# Sheet1.net
KiCad netlist of a schematic drawn in Altium Designer
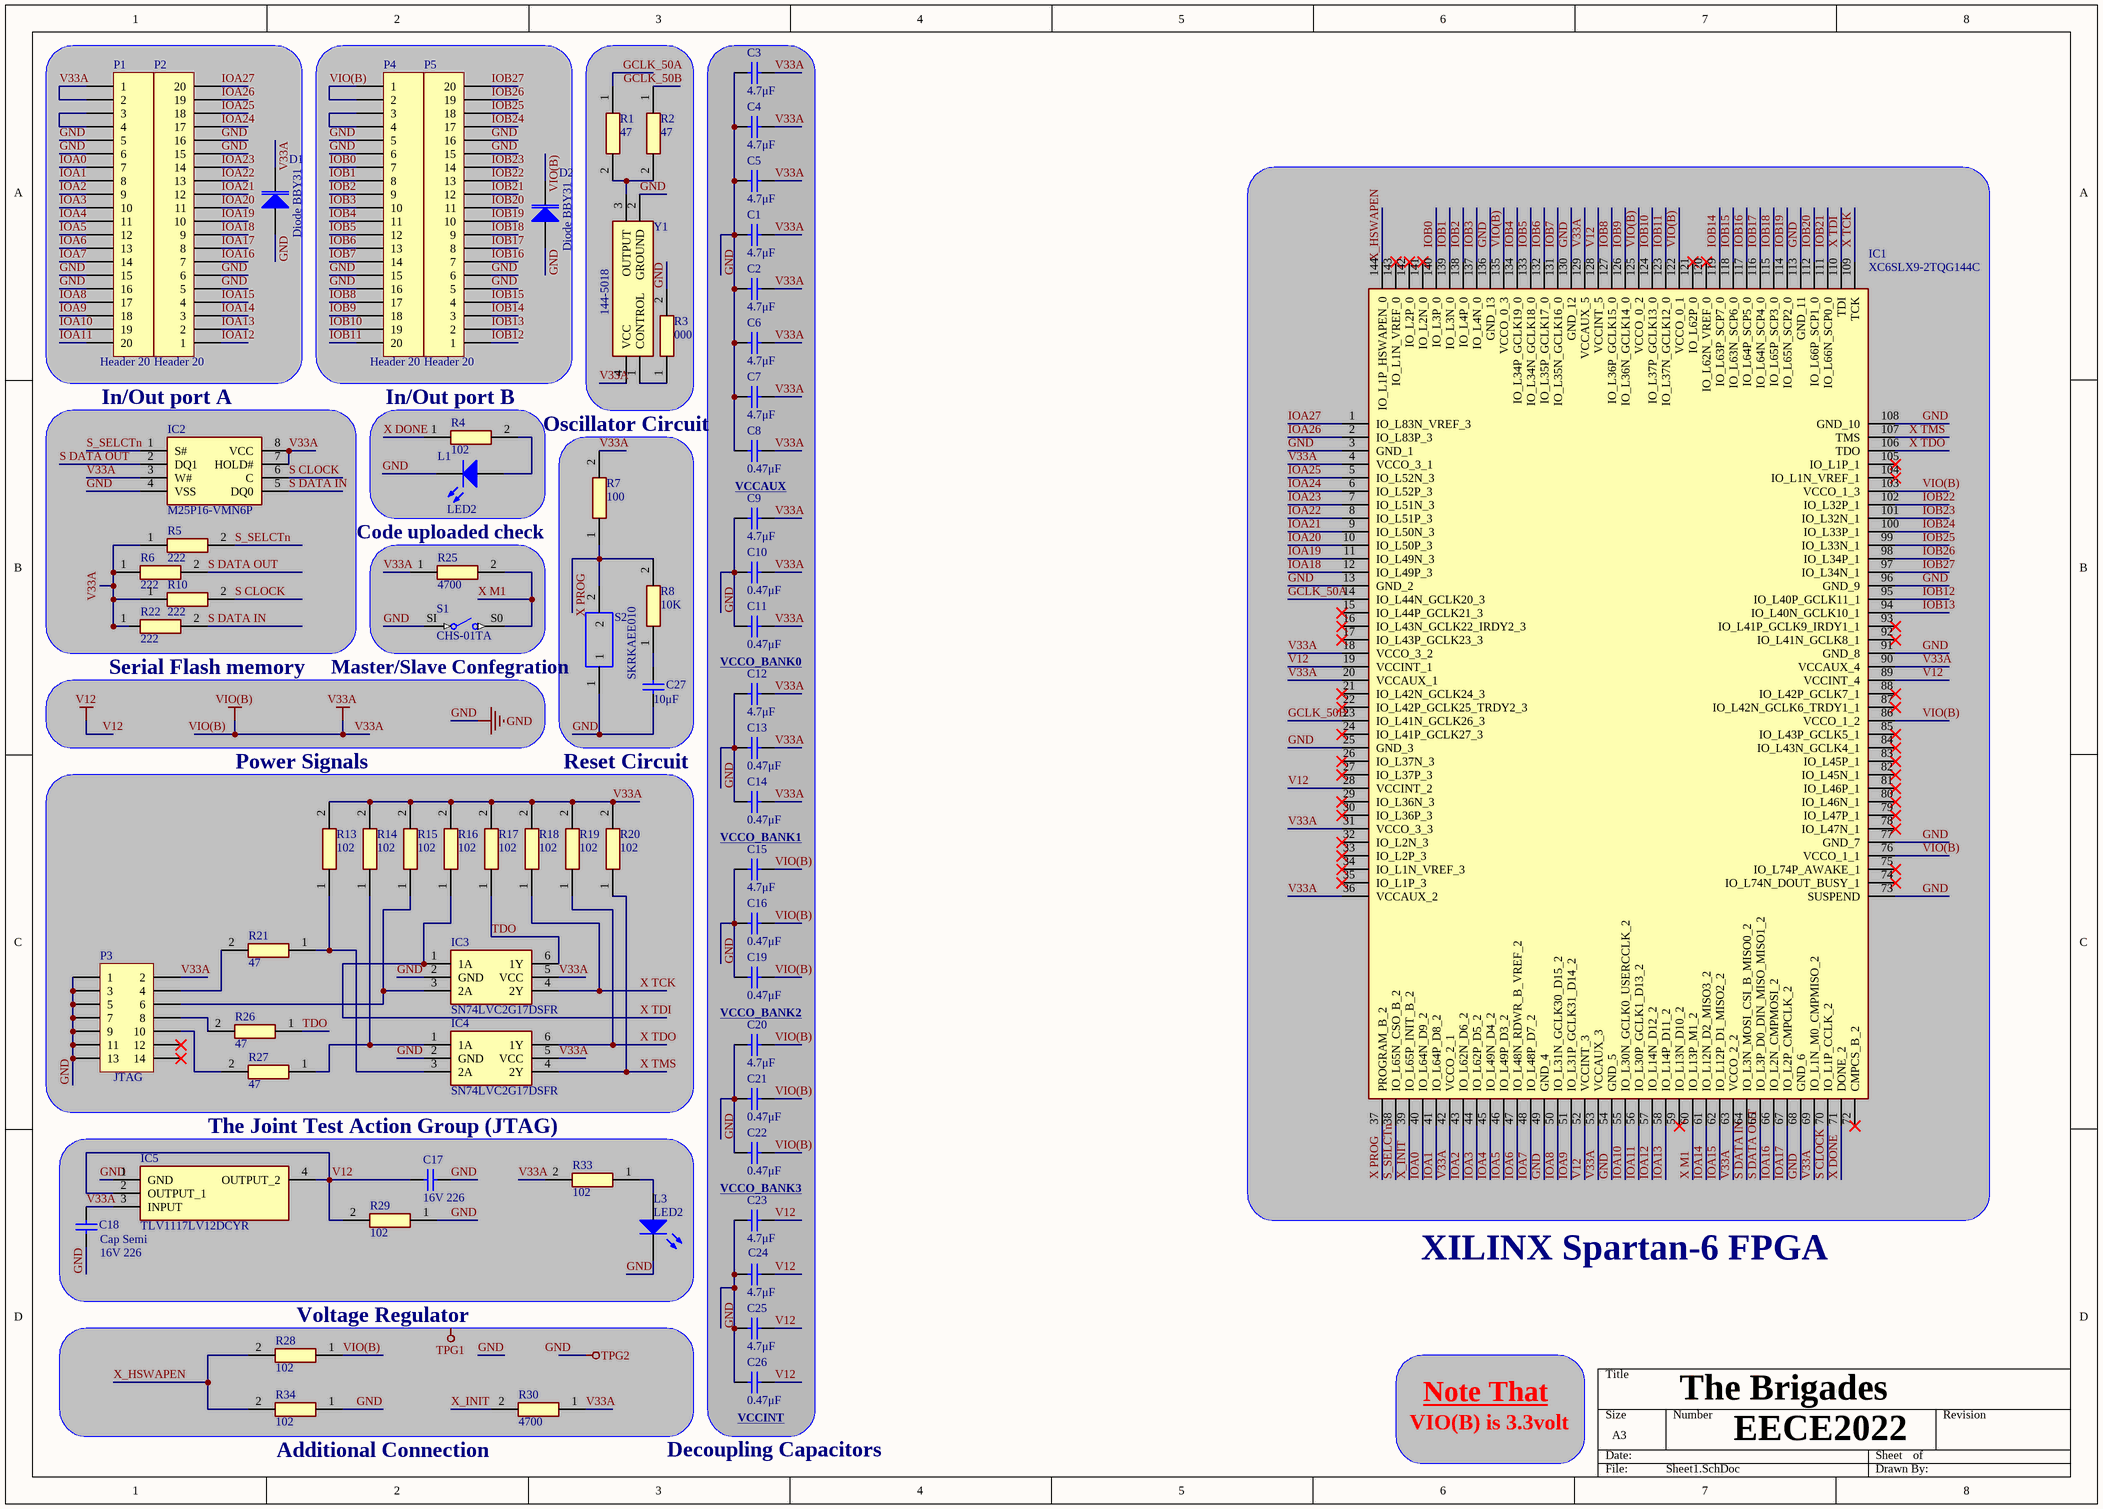
[diagram p0: Sheet1.SchDoc]

(export (version "E")
  (design (tool "Eeschema 10.0.6"))
  (components
    (comp (ref "C1")
      (value "4.7μF")
      (footprint "0402")
      (description "Capacitor (Semiconductor SIM Model)")
      (fields (field (name "PUBLISHER") "Altium Limited"))
      (libsource (lib "Miscellaneous Devices") (part "Cap Semi"))
    )
    (comp (ref "C2")
      (value "4.7μF")
      (footprint "0402")
      (description "Capacitor (Semiconductor SIM Model)")
      (fields (field (name "PUBLISHER") "Altium Limited"))
      (libsource (lib "Miscellaneous Devices") (part "Cap Semi"))
    )
    (comp (ref "C3")
      (value "4.7μF")
      (footprint "0402")
      (description "Capacitor (Semiconductor SIM Model)")
      (fields (field (name "PUBLISHER") "Altium Limited"))
      (libsource (lib "Miscellaneous Devices") (part "Cap Semi"))
    )
    (comp (ref "C4")
      (value "4.7μF")
      (footprint "0402")
      (description "Capacitor (Semiconductor SIM Model)")
      (fields (field (name "PUBLISHER") "Altium Limited"))
      (libsource (lib "Miscellaneous Devices") (part "Cap Semi"))
    )
    (comp (ref "C5")
      (value "4.7μF")
      (footprint "0402")
      (description "Capacitor (Semiconductor SIM Model)")
      (fields (field (name "PUBLISHER") "Altium Limited"))
      (libsource (lib "Miscellaneous Devices") (part "Cap Semi"))
    )
    (comp (ref "C6")
      (value "4.7μF")
      (footprint "0402")
      (description "Capacitor (Semiconductor SIM Model)")
      (fields (field (name "PUBLISHER") "Altium Limited"))
      (libsource (lib "Miscellaneous Devices") (part "Cap Semi"))
    )
    (comp (ref "C7")
      (value "4.7μF")
      (footprint "0402")
      (description "Capacitor (Semiconductor SIM Model)")
      (fields (field (name "PUBLISHER") "Altium Limited"))
      (libsource (lib "Miscellaneous Devices") (part "Cap Semi"))
    )
    (comp (ref "C8")
      (value "0.47μF")
      (footprint "0402")
      (description "Capacitor (Semiconductor SIM Model)")
      (fields (field (name "PUBLISHER") "Altium Limited"))
      (libsource (lib "Miscellaneous Devices") (part "Cap Semi"))
    )
    (comp (ref "C9")
      (value "4.7μF")
      (footprint "0402")
      (description "Capacitor (Semiconductor SIM Model)")
      (fields (field (name "PUBLISHER") "Altium Limited"))
      (libsource (lib "Miscellaneous Devices") (part "Cap Semi"))
    )
    (comp (ref "C10")
      (value "0.47μF")
      (footprint "0402")
      (description "Capacitor (Semiconductor SIM Model)")
      (fields (field (name "PUBLISHER") "Altium Limited"))
      (libsource (lib "Miscellaneous Devices") (part "Cap Semi"))
    )
    (comp (ref "C11")
      (value "0.47μF")
      (footprint "0402")
      (description "Capacitor (Semiconductor SIM Model)")
      (fields (field (name "PUBLISHER") "Altium Limited"))
      (libsource (lib "Miscellaneous Devices") (part "Cap Semi"))
    )
    (comp (ref "C12")
      (value "4.7μF")
      (footprint "0402")
      (description "Capacitor (Semiconductor SIM Model)")
      (fields (field (name "PUBLISHER") "Altium Limited"))
      (libsource (lib "Miscellaneous Devices") (part "Cap Semi"))
    )
    (comp (ref "C13")
      (value "0.47μF")
      (footprint "0402")
      (description "Capacitor (Semiconductor SIM Model)")
      (fields (field (name "PUBLISHER") "Altium Limited"))
      (libsource (lib "Miscellaneous Devices") (part "Cap Semi"))
    )
    (comp (ref "C14")
      (value "0.47μF")
      (footprint "0402")
      (description "Capacitor (Semiconductor SIM Model)")
      (fields (field (name "PUBLISHER") "Altium Limited"))
      (libsource (lib "Miscellaneous Devices") (part "Cap Semi"))
    )
    (comp (ref "C15")
      (value "4.7μF")
      (footprint "0402")
      (description "Capacitor (Semiconductor SIM Model)")
      (fields (field (name "PUBLISHER") "Altium Limited"))
      (libsource (lib "Miscellaneous Devices") (part "Cap Semi"))
    )
    (comp (ref "C16")
      (value "0.47μF")
      (footprint "0402")
      (description "Capacitor (Semiconductor SIM Model)")
      (fields (field (name "PUBLISHER") "Altium Limited"))
      (libsource (lib "Miscellaneous Devices") (part "Cap Semi"))
    )
    (comp (ref "C17")
      (value "16V 226")
      (footprint "0402")
      (description "Capacitor (Semiconductor SIM Model)")
      (fields (field (name "PUBLISHER") "Altium Limited"))
      (libsource (lib "Miscellaneous Devices") (part "Cap Semi"))
    )
    (comp (ref "C18")
      (value "Cap Semi")
      (footprint "0402")
      (description "Capacitor (Semiconductor SIM Model)")
      (fields (field (name "ALTIUM_VALUE") "16V 226") (field (name "PUBLISHER") "Altium Limited"))
      (libsource (lib "Miscellaneous Devices") (part "Cap Semi"))
    )
    (comp (ref "C19")
      (value "0.47μF")
      (footprint "0402")
      (description "Capacitor (Semiconductor SIM Model)")
      (fields (field (name "PUBLISHER") "Altium Limited"))
      (libsource (lib "Miscellaneous Devices") (part "Cap Semi"))
    )
    (comp (ref "C20")
      (value "4.7μF")
      (footprint "0402")
      (description "Capacitor (Semiconductor SIM Model)")
      (fields (field (name "PUBLISHER") "Altium Limited"))
      (libsource (lib "Miscellaneous Devices") (part "Cap Semi"))
    )
    (comp (ref "C21")
      (value "0.47μF")
      (footprint "0402")
      (description "Capacitor (Semiconductor SIM Model)")
      (fields (field (name "PUBLISHER") "Altium Limited"))
      (libsource (lib "Miscellaneous Devices") (part "Cap Semi"))
    )
    (comp (ref "C22")
      (value "0.47μF")
      (footprint "0402")
      (description "Capacitor (Semiconductor SIM Model)")
      (fields (field (name "PUBLISHER") "Altium Limited"))
      (libsource (lib "Miscellaneous Devices") (part "Cap Semi"))
    )
    (comp (ref "C23")
      (value "4.7μF")
      (footprint "0402")
      (description "Capacitor (Semiconductor SIM Model)")
      (fields (field (name "PUBLISHER") "Altium Limited"))
      (libsource (lib "Miscellaneous Devices") (part "Cap Semi"))
    )
    (comp (ref "C24")
      (value "4.7μF")
      (footprint "0402")
      (description "Capacitor (Semiconductor SIM Model)")
      (fields (field (name "PUBLISHER") "Altium Limited"))
      (libsource (lib "Miscellaneous Devices") (part "Cap Semi"))
    )
    (comp (ref "C25")
      (value "4.7μF")
      (footprint "0402")
      (description "Capacitor (Semiconductor SIM Model)")
      (fields (field (name "PUBLISHER") "Altium Limited"))
      (libsource (lib "Miscellaneous Devices") (part "Cap Semi"))
    )
    (comp (ref "C26")
      (value "0.47μF")
      (footprint "0402")
      (description "Capacitor (Semiconductor SIM Model)")
      (fields (field (name "PUBLISHER") "Altium Limited"))
      (libsource (lib "Miscellaneous Devices") (part "Cap Semi"))
    )
    (comp (ref "C27")
      (value "10μF")
      (footprint "0402")
      (description "Capacitor (Semiconductor SIM Model)")
      (fields (field (name "PUBLISHER") "Altium Limited"))
      (libsource (lib "Miscellaneous Devices") (part "Cap Semi"))
    )
    (comp (ref "D1")
      (value "Diode BBY31")
      (footprint "SOT23_N")
      (description "SOT23 Silicon Planar Variable Capacitance Diode")
      (fields (field (name "PUBLISHER") "Altium Limited"))
      (libsource (lib "Miscellaneous Devices") (part "Diode BBY31"))
    )
    (comp (ref "D2")
      (value "Diode BBY31")
      (footprint "SOT23_N")
      (description "SOT23 Silicon Planar Variable Capacitance Diode")
      (fields (field (name "PUBLISHER") "Altium Limited"))
      (libsource (lib "Miscellaneous Devices") (part "Diode BBY31"))
    )
    (comp (ref "IC1")
      (value "XC6SLX9-2TQG144C")
      (footprint "SamacSys:QFP50P2200X2200X160-144N")
      (description "Integrated Circuit")
      (fields
        (field (name "MOUSER PART NUMBER") "217-XC6SLX9-2TQG144C")
        (field (name "RS PART NUMBER") "7276011P")
      )
      (libsource (lib "*") (part "XC6SLX9-2TQG144C"))
    )
    (comp (ref "IC2")
      (value "M25P16-VMN6P")
      (footprint "SamacSys:SOIC127P600X175-8N")
      (description "Integrated Circuit")
      (fields (field (name "MOUSER PART NUMBER") "340-180484") (field (name "RS PART NUMBER") "7824601P"))
      (libsource (lib "*") (part "M25P16-VMN6P"))
    )
    (comp (ref "IC3")
      (value "SN74LVC2G17DSFR")
      (footprint "SamacSys:SON35P100X100X40-6N")
      (description "Integrated Circuit")
      (fields (field (name "MOUSER PART NUMBER") "595-SN74LVC2G17DSFR"))
      (libsource (lib "*") (part "SN74LVC2G17DSFR"))
    )
    (comp (ref "IC4")
      (value "SN74LVC2G17DSFR")
      (footprint "SamacSys:SON35P100X100X40-6N")
      (description "Integrated Circuit")
      (fields (field (name "MOUSER PART NUMBER") "595-SN74LVC2G17DSFR"))
      (libsource (lib "*") (part "SN74LVC2G17DSFR"))
    )
    (comp (ref "IC5")
      (value "TLV1117LV12DCYR")
      (footprint "SamacSys:SOT230P700X180-4N")
      (description "Integrated Circuit")
      (fields
        (field (name "MOUSER PART NUMBER") "595-TLV1117LV12DCYR")
        (field (name "RS PART NUMBER") "8253628P")
      )
      (libsource (lib "*") (part "TLV1117LV12DCYR"))
    )
    (comp (ref "L1")
      (value "LED2")
      (footprint "3.2X1.6X1.1")
      (description "Typical RED, GREEN, YELLOW, AMBER GaAs LED")
      (fields (field (name "PUBLISHER") "Altium Limited"))
      (libsource (lib "Miscellaneous Devices") (part "LED2"))
    )
    (comp (ref "L3")
      (value "LED2")
      (footprint "3.2X1.6X1.1")
      (description "Typical RED, GREEN, YELLOW, AMBER GaAs LED")
      (fields (field (name "PUBLISHER") "Altium Limited"))
      (libsource (lib "Miscellaneous Devices") (part "LED2"))
    )
    (comp (ref "P1")
      (value "Header 20")
      (footprint "HDR1X20")
      (description "Header, 20-Pin")
      (fields (field (name "PUBLISHER") "Altium Limited"))
      (libsource (lib "") (part "Header 20_1"))
    )
    (comp (ref "P2")
      (value "Header 20")
      (footprint "HDR1X20")
      (description "Header, 20-Pin")
      (fields (field (name "PUBLISHER") "Altium Limited"))
      (libsource (lib "Miscellaneous Connectors") (part "Header 20"))
    )
    (comp (ref "P3")
      (value "JTAG")
      (footprint "HDR2X7H")
      (description "Header, 7-Pin, Dual row, Right Angle")
      (fields (field (name "PUBLISHER") "Altium Limited"))
      (libsource (lib "Miscellaneous Connectors") (part "Header 7X2H"))
    )
    (comp (ref "P4")
      (value "Header 20")
      (footprint "HDR1X20")
      (description "Header, 20-Pin")
      (fields (field (name "PUBLISHER") "Altium Limited"))
      (libsource (lib "") (part "Header 20_1"))
    )
    (comp (ref "P5")
      (value "Header 20")
      (footprint "HDR1X20")
      (description "Header, 20-Pin")
      (fields (field (name "PUBLISHER") "Altium Limited"))
      (libsource (lib "Miscellaneous Connectors") (part "Header 20"))
    )
    (comp (ref "R1")
      (value "47")
      (footprint "SamacSys:RESC0603X28N")
      (description "Resistor")
      (fields
        (field (name "MANUFACTURER_PART_NUMBER") "CPF0201D100RE1")
        (field (name "MOUSER PART NUMBER") "279-CPF0201D100RE1")
      )
      (libsource (lib "") (part "CPF0201D100RE1_3"))
    )
    (comp (ref "R2")
      (value "47")
      (footprint "SamacSys:RESC0603X28N")
      (description "Resistor")
      (fields
        (field (name "MANUFACTURER_PART_NUMBER") "CPF0201D100RE1")
        (field (name "MOUSER PART NUMBER") "279-CPF0201D100RE1")
      )
      (libsource (lib "") (part "CPF0201D100RE1_3"))
    )
    (comp (ref "R3")
      (value "000")
      (footprint "SamacSys:RESC0603X28N")
      (description "Resistor")
      (fields
        (field (name "MANUFACTURER_PART_NUMBER") "CPF0201D100RE1")
        (field (name "MOUSER PART NUMBER") "279-CPF0201D100RE1")
      )
      (libsource (lib "") (part "CPF0201D100RE1_2"))
    )
    (comp (ref "R4")
      (value "102")
      (footprint "SamacSys:RESC0603X28N")
      (description "Resistor")
      (fields
        (field (name "MANUFACTURER_PART_NUMBER") "CPF0201D100RE1")
        (field (name "MOUSER PART NUMBER") "279-CPF0201D100RE1")
      )
      (libsource (lib "*") (part "CPF0201D100RE1"))
    )
    (comp (ref "R5")
      (value "222")
      (footprint "SamacSys:RESC0603X28N")
      (description "Resistor")
      (fields
        (field (name "MANUFACTURER_PART_NUMBER") "CPF0201D100RE1")
        (field (name "MOUSER PART NUMBER") "279-CPF0201D100RE1")
      )
      (libsource (lib "*") (part "CPF0201D100RE1"))
    )
    (comp (ref "R6")
      (value "222")
      (footprint "SamacSys:RESC0603X28N")
      (description "Resistor")
      (fields
        (field (name "MANUFACTURER_PART_NUMBER") "CPF0201D100RE1")
        (field (name "MOUSER PART NUMBER") "279-CPF0201D100RE1")
      )
      (libsource (lib "*") (part "CPF0201D100RE1"))
    )
    (comp (ref "R7")
      (value "100")
      (footprint "SamacSys:RESC0603X28N")
      (description "Resistor")
      (fields
        (field (name "MANUFACTURER_PART_NUMBER") "CPF0201D100RE1")
        (field (name "MOUSER PART NUMBER") "279-CPF0201D100RE1")
      )
      (libsource (lib "") (part "CPF0201D100RE1_2"))
    )
    (comp (ref "R8")
      (value "10K")
      (footprint "SamacSys:RESC0603X28N")
      (description "Resistor")
      (fields
        (field (name "MANUFACTURER_PART_NUMBER") "CPF0201D100RE1")
        (field (name "MOUSER PART NUMBER") "279-CPF0201D100RE1")
      )
      (libsource (lib "") (part "CPF0201D100RE1_2"))
    )
    (comp (ref "R10")
      (value "222")
      (footprint "SamacSys:RESC0603X28N")
      (description "Resistor")
      (fields
        (field (name "MANUFACTURER_PART_NUMBER") "CPF0201D100RE1")
        (field (name "MOUSER PART NUMBER") "279-CPF0201D100RE1")
      )
      (libsource (lib "*") (part "CPF0201D100RE1"))
    )
    (comp (ref "R13")
      (value "102")
      (footprint "SamacSys:RESC0603X28N")
      (description "Resistor")
      (fields
        (field (name "MANUFACTURER_PART_NUMBER") "CPF0201D100RE1")
        (field (name "MOUSER PART NUMBER") "279-CPF0201D100RE1")
      )
      (libsource (lib "") (part "CPF0201D100RE1_2"))
    )
    (comp (ref "R14")
      (value "102")
      (footprint "SamacSys:RESC0603X28N")
      (description "Resistor")
      (fields
        (field (name "MANUFACTURER_PART_NUMBER") "CPF0201D100RE1")
        (field (name "MOUSER PART NUMBER") "279-CPF0201D100RE1")
      )
      (libsource (lib "") (part "CPF0201D100RE1_2"))
    )
    (comp (ref "R15")
      (value "102")
      (footprint "SamacSys:RESC0603X28N")
      (description "Resistor")
      (fields
        (field (name "MANUFACTURER_PART_NUMBER") "CPF0201D100RE1")
        (field (name "MOUSER PART NUMBER") "279-CPF0201D100RE1")
      )
      (libsource (lib "") (part "CPF0201D100RE1_2"))
    )
    (comp (ref "R16")
      (value "102")
      (footprint "SamacSys:RESC0603X28N")
      (description "Resistor")
      (fields
        (field (name "MANUFACTURER_PART_NUMBER") "CPF0201D100RE1")
        (field (name "MOUSER PART NUMBER") "279-CPF0201D100RE1")
      )
      (libsource (lib "") (part "CPF0201D100RE1_2"))
    )
    (comp (ref "R17")
      (value "102")
      (footprint "SamacSys:RESC0603X28N")
      (description "Resistor")
      (fields
        (field (name "MANUFACTURER_PART_NUMBER") "CPF0201D100RE1")
        (field (name "MOUSER PART NUMBER") "279-CPF0201D100RE1")
      )
      (libsource (lib "") (part "CPF0201D100RE1_2"))
    )
    (comp (ref "R18")
      (value "102")
      (footprint "SamacSys:RESC0603X28N")
      (description "Resistor")
      (fields
        (field (name "MANUFACTURER_PART_NUMBER") "CPF0201D100RE1")
        (field (name "MOUSER PART NUMBER") "279-CPF0201D100RE1")
      )
      (libsource (lib "") (part "CPF0201D100RE1_2"))
    )
    (comp (ref "R19")
      (value "102")
      (footprint "SamacSys:RESC0603X28N")
      (description "Resistor")
      (fields
        (field (name "MANUFACTURER_PART_NUMBER") "CPF0201D100RE1")
        (field (name "MOUSER PART NUMBER") "279-CPF0201D100RE1")
      )
      (libsource (lib "") (part "CPF0201D100RE1_2"))
    )
    (comp (ref "R20")
      (value "102")
      (footprint "SamacSys:RESC0603X28N")
      (description "Resistor")
      (fields
        (field (name "MANUFACTURER_PART_NUMBER") "CPF0201D100RE1")
        (field (name "MOUSER PART NUMBER") "279-CPF0201D100RE1")
      )
      (libsource (lib "") (part "CPF0201D100RE1_2"))
    )
    (comp (ref "R21")
      (value "47")
      (footprint "SamacSys:RESC0603X28N")
      (description "Resistor")
      (fields
        (field (name "MANUFACTURER_PART_NUMBER") "CPF0201D100RE1")
        (field (name "MOUSER PART NUMBER") "279-CPF0201D100RE1")
      )
      (libsource (lib "") (part "CPF0201D100RE1_1"))
    )
    (comp (ref "R22")
      (value "222")
      (footprint "SamacSys:RESC0603X28N")
      (description "Resistor")
      (fields
        (field (name "MANUFACTURER_PART_NUMBER") "CPF0201D100RE1")
        (field (name "MOUSER PART NUMBER") "279-CPF0201D100RE1")
      )
      (libsource (lib "*") (part "CPF0201D100RE1"))
    )
    (comp (ref "R25")
      (value "4700")
      (footprint "SamacSys:RESC0603X28N")
      (description "Resistor")
      (fields
        (field (name "MANUFACTURER_PART_NUMBER") "CPF0201D100RE1")
        (field (name "MOUSER PART NUMBER") "279-CPF0201D100RE1")
      )
      (libsource (lib "*") (part "CPF0201D100RE1"))
    )
    (comp (ref "R26")
      (value "47")
      (footprint "SamacSys:RESC0603X28N")
      (description "Resistor")
      (fields
        (field (name "MANUFACTURER_PART_NUMBER") "CPF0201D100RE1")
        (field (name "MOUSER PART NUMBER") "279-CPF0201D100RE1")
      )
      (libsource (lib "") (part "CPF0201D100RE1_1"))
    )
    (comp (ref "R27")
      (value "47")
      (footprint "SamacSys:RESC0603X28N")
      (description "Resistor")
      (fields
        (field (name "MANUFACTURER_PART_NUMBER") "CPF0201D100RE1")
        (field (name "MOUSER PART NUMBER") "279-CPF0201D100RE1")
      )
      (libsource (lib "") (part "CPF0201D100RE1_1"))
    )
    (comp (ref "R28")
      (value "102")
      (footprint "SamacSys:RESC0603X28N")
      (description "Resistor")
      (fields
        (field (name "MANUFACTURER_PART_NUMBER") "CPF0201D100RE1")
        (field (name "MOUSER PART NUMBER") "279-CPF0201D100RE1")
      )
      (libsource (lib "") (part "CPF0201D100RE1_1"))
    )
    (comp (ref "R29")
      (value "102")
      (footprint "SamacSys:RESC0603X28N")
      (description "Resistor")
      (fields
        (field (name "MANUFACTURER_PART_NUMBER") "CPF0201D100RE1")
        (field (name "MOUSER PART NUMBER") "279-CPF0201D100RE1")
      )
      (libsource (lib "") (part "CPF0201D100RE1_1"))
    )
    (comp (ref "R30")
      (value "4700")
      (footprint "SamacSys:RESC0603X28N")
      (description "Resistor")
      (fields
        (field (name "MANUFACTURER_PART_NUMBER") "CPF0201D100RE1")
        (field (name "MOUSER PART NUMBER") "279-CPF0201D100RE1")
      )
      (libsource (lib "") (part "CPF0201D100RE1_1"))
    )
    (comp (ref "R33")
      (value "102")
      (footprint "SamacSys:RESC0603X28N")
      (description "Resistor")
      (fields
        (field (name "MANUFACTURER_PART_NUMBER") "CPF0201D100RE1")
        (field (name "MOUSER PART NUMBER") "279-CPF0201D100RE1")
      )
      (libsource (lib "") (part "CPF0201D100RE1_1"))
    )
    (comp (ref "R34")
      (value "102")
      (footprint "SamacSys:RESC0603X28N")
      (description "Resistor")
      (fields
        (field (name "MANUFACTURER_PART_NUMBER") "CPF0201D100RE1")
        (field (name "MOUSER PART NUMBER") "279-CPF0201D100RE1")
      )
      (libsource (lib "") (part "CPF0201D100RE1_1"))
    )
    (comp (ref "S1")
      (value "CHS-01TA")
      (footprint "CHS-01TA")
      (description "Dip Switch SPST 1 Position Surface Mount Slide _Standard_ Actuator 100mA 6VDC")
      (fields (field (name "MF") "Nidec Copal"))
      (libsource (lib "CHS-01TA") (part "CHS-01TA"))
    )
    (comp (ref "S2")
      (value "SKRKAEE010")
      (footprint "SKRK")
      (description "Switch Tactile N.O. SPST Round Button Gull Wing 0.05A 12VDC 1.57N SMD T/R")
      (fields (field (name "MF") "ALPS"))
      (libsource (lib "SKRKAEE010") (part "SKRKAEE010"))
    )
    (comp (ref "Y1")
      (value "144-5018")
      (footprint "SamacSys:1445018")
      (description "Crystal or Oscillator")
      (libsource (lib "*") (part "144-5018"))
    )
  )
  (nets
    (net (code "1") (name "/GCLK_50A") (class "Default")
      (node (ref "IC1") (pin "14") (pinfunction "IO_L44N_GCLK20_3_14") (pintype "passive"))
      (node (ref "R1") (pin "1") (pinfunction "1_1") (pintype "passive"))
    )
    (net (code "2") (name "/GCLK_50B") (class "Default")
      (node (ref "IC1") (pin "23") (pinfunction "IO_L41N_GCLK26_3_23") (pintype "passive"))
      (node (ref "R2") (pin "1") (pinfunction "1_1") (pintype "passive"))
    )
    (net (code "3") (name "/IOA0") (class "Default")
      (node (ref "IC1") (pin "40") (pinfunction "IO_L64N_D9_2_40") (pintype "passive"))
      (node (ref "P1") (pin "7") (pinfunction "7_7") (pintype "passive"))
    )
    (net (code "4") (name "/IOA1") (class "Default")
      (node (ref "IC1") (pin "41") (pinfunction "IO_L64P_D8_2_41") (pintype "passive"))
      (node (ref "P1") (pin "8") (pinfunction "8_8") (pintype "passive"))
    )
    (net (code "5") (name "/IOA2") (class "Default")
      (node (ref "IC1") (pin "43") (pinfunction "IO_L62N_D6_2_43") (pintype "passive"))
      (node (ref "P1") (pin "9") (pinfunction "9_9") (pintype "passive"))
    )
    (net (code "6") (name "/IOA3") (class "Default")
      (node (ref "IC1") (pin "44") (pinfunction "IO_L62P_D5_2_44") (pintype "passive"))
      (node (ref "P1") (pin "10") (pinfunction "10_10") (pintype "passive"))
    )
    (net (code "7") (name "/IOA4") (class "Default")
      (node (ref "IC1") (pin "45") (pinfunction "IO_L49N_D4_2_45") (pintype "passive"))
      (node (ref "P1") (pin "11") (pinfunction "11_11") (pintype "passive"))
    )
    (net (code "8") (name "/IOA5") (class "Default")
      (node (ref "IC1") (pin "46") (pinfunction "IO_L49P_D3_2_46") (pintype "passive"))
      (node (ref "P1") (pin "12") (pinfunction "12_12") (pintype "passive"))
    )
    (net (code "9") (name "/IOA6") (class "Default")
      (node (ref "IC1") (pin "47") (pinfunction "IO_L48N_RDWR_B_VREF_2_47") (pintype "passive"))
      (node (ref "P1") (pin "13") (pinfunction "13_13") (pintype "passive"))
    )
    (net (code "10") (name "/IOA7") (class "Default")
      (node (ref "IC1") (pin "48") (pinfunction "IO_L48P_D7_2_48") (pintype "passive"))
      (node (ref "P1") (pin "14") (pinfunction "14_14") (pintype "passive"))
    )
    (net (code "11") (name "/IOA8") (class "Default")
      (node (ref "IC1") (pin "50") (pinfunction "IO_L31N_GCLK30_D15_2_50") (pintype "passive"))
      (node (ref "P1") (pin "17") (pinfunction "17_17") (pintype "passive"))
    )
    (net (code "12") (name "/IOA9") (class "Default")
      (node (ref "IC1") (pin "51") (pinfunction "IO_L31P_GCLK31_D14_2_51") (pintype "passive"))
      (node (ref "P1") (pin "18") (pinfunction "18_18") (pintype "passive"))
    )
    (net (code "13") (name "/IOA10") (class "Default")
      (node (ref "IC1") (pin "55") (pinfunction "IO_L30N_GCLK0_USERCCLK_2_55") (pintype "passive"))
      (node (ref "P1") (pin "19") (pinfunction "19_19") (pintype "passive"))
    )
    (net (code "14") (name "/IOA11") (class "Default")
      (node (ref "IC1") (pin "56") (pinfunction "IO_L30P_GCLK1_D13_2_56") (pintype "passive"))
      (node (ref "P1") (pin "20") (pinfunction "20_20") (pintype "passive"))
    )
    (net (code "15") (name "/IOA12") (class "Default")
      (node (ref "IC1") (pin "57") (pinfunction "IO_L14N_D12_2_57") (pintype "passive"))
      (node (ref "P2") (pin "1") (pinfunction "1_1") (pintype "passive"))
    )
    (net (code "16") (name "/IOA13") (class "Default")
      (node (ref "IC1") (pin "58") (pinfunction "IO_L14P_D11_2_58") (pintype "passive"))
      (node (ref "P2") (pin "2") (pinfunction "2_2") (pintype "passive"))
    )
    (net (code "17") (name "/IOA14") (class "Default")
      (node (ref "IC1") (pin "61") (pinfunction "IO_L12N_D2_MISO3_2_61") (pintype "passive"))
      (node (ref "P2") (pin "3") (pinfunction "3_3") (pintype "passive"))
    )
    (net (code "18") (name "/IOA15") (class "Default")
      (node (ref "IC1") (pin "62") (pinfunction "IO_L12P_D1_MISO2_2_62") (pintype "passive"))
      (node (ref "P2") (pin "4") (pinfunction "4_4") (pintype "passive"))
    )
    (net (code "19") (name "/IOA16") (class "Default")
      (node (ref "IC1") (pin "66") (pinfunction "IO_L2N_CMPMOSI_2_66") (pintype "passive"))
      (node (ref "P2") (pin "7") (pinfunction "7_7") (pintype "passive"))
    )
    (net (code "20") (name "/IOA17") (class "Default")
      (node (ref "IC1") (pin "67") (pinfunction "IO_L2P_CMPCLK_2_67") (pintype "passive"))
      (node (ref "P2") (pin "8") (pinfunction "8_8") (pintype "passive"))
    )
    (net (code "21") (name "/IOA18") (class "Default")
      (node (ref "IC1") (pin "12") (pinfunction "IO_L49P_3_12") (pintype "passive"))
      (node (ref "P2") (pin "9") (pinfunction "9_9") (pintype "passive"))
    )
    (net (code "22") (name "/IOA19") (class "Default")
      (node (ref "IC1") (pin "11") (pinfunction "IO_L49N_3_11") (pintype "passive"))
      (node (ref "P2") (pin "10") (pinfunction "10_10") (pintype "passive"))
    )
    (net (code "23") (name "/IOA20") (class "Default")
      (node (ref "IC1") (pin "10") (pinfunction "IO_L50P_3_10") (pintype "passive"))
      (node (ref "P2") (pin "11") (pinfunction "11_11") (pintype "passive"))
    )
    (net (code "24") (name "/IOA21") (class "Default")
      (node (ref "IC1") (pin "9") (pinfunction "IO_L50N_3_9") (pintype "passive"))
      (node (ref "P2") (pin "12") (pinfunction "12_12") (pintype "passive"))
    )
    (net (code "25") (name "/IOA22") (class "Default")
      (node (ref "IC1") (pin "8") (pinfunction "IO_L51P_3_8") (pintype "passive"))
      (node (ref "P2") (pin "13") (pinfunction "13_13") (pintype "passive"))
    )
    (net (code "26") (name "/IOA23") (class "Default")
      (node (ref "IC1") (pin "7") (pinfunction "IO_L51N_3_7") (pintype "passive"))
      (node (ref "P2") (pin "14") (pinfunction "14_14") (pintype "passive"))
    )
    (net (code "27") (name "/IOA24") (class "Default")
      (node (ref "IC1") (pin "6") (pinfunction "IO_L52P_3_6") (pintype "passive"))
      (node (ref "P2") (pin "17") (pinfunction "17_17") (pintype "passive"))
    )
    (net (code "28") (name "/IOA25") (class "Default")
      (node (ref "IC1") (pin "5") (pinfunction "IO_L52N_3_5") (pintype "passive"))
      (node (ref "P2") (pin "18") (pinfunction "18_18") (pintype "passive"))
    )
    (net (code "29") (name "/IOA26") (class "Default")
      (node (ref "IC1") (pin "2") (pinfunction "IO_L83P_3_2") (pintype "passive"))
      (node (ref "P2") (pin "19") (pinfunction "19_19") (pintype "passive"))
    )
    (net (code "30") (name "/IOA27") (class "Default")
      (node (ref "IC1") (pin "1") (pinfunction "IO_L83N_VREF_3_1") (pintype "passive"))
      (node (ref "P2") (pin "20") (pinfunction "20_20") (pintype "passive"))
    )
    (net (code "31") (name "/IOB0") (class "Default")
      (node (ref "IC1") (pin "140") (pinfunction "IO_L3P_0_140") (pintype "passive"))
      (node (ref "P4") (pin "7") (pinfunction "7_7") (pintype "passive"))
    )
    (net (code "32") (name "/IOB1") (class "Default")
      (node (ref "IC1") (pin "139") (pinfunction "IO_L3N_0_139") (pintype "passive"))
      (node (ref "P4") (pin "8") (pinfunction "8_8") (pintype "passive"))
    )
    (net (code "33") (name "/IOB2") (class "Default")
      (node (ref "IC1") (pin "138") (pinfunction "IO_L4P_0_138") (pintype "passive"))
      (node (ref "P4") (pin "9") (pinfunction "9_9") (pintype "passive"))
    )
    (net (code "34") (name "/IOB3") (class "Default")
      (node (ref "IC1") (pin "137") (pinfunction "IO_L4N_0_137") (pintype "passive"))
      (node (ref "P4") (pin "10") (pinfunction "10_10") (pintype "passive"))
    )
    (net (code "35") (name "/IOB4") (class "Default")
      (node (ref "IC1") (pin "134") (pinfunction "IO_L34P_GCLK19_0_134") (pintype "passive"))
      (node (ref "P4") (pin "11") (pinfunction "11_11") (pintype "passive"))
    )
    (net (code "36") (name "/IOB5") (class "Default")
      (node (ref "IC1") (pin "133") (pinfunction "IO_L34N_GCLK18_0_133") (pintype "passive"))
      (node (ref "P4") (pin "12") (pinfunction "12_12") (pintype "passive"))
    )
    (net (code "37") (name "/IOB6") (class "Default")
      (node (ref "IC1") (pin "132") (pinfunction "IO_L35P_GCLK17_0_132") (pintype "passive"))
      (node (ref "P4") (pin "13") (pinfunction "13_13") (pintype "passive"))
    )
    (net (code "38") (name "/IOB7") (class "Default")
      (node (ref "IC1") (pin "131") (pinfunction "IO_L35N_GCLK16_0_131") (pintype "passive"))
      (node (ref "P4") (pin "14") (pinfunction "14_14") (pintype "passive"))
    )
    (net (code "39") (name "/IOB8") (class "Default")
      (node (ref "IC1") (pin "127") (pinfunction "IO_L36P_GCLK15_0_127") (pintype "passive"))
      (node (ref "P4") (pin "17") (pinfunction "17_17") (pintype "passive"))
    )
    (net (code "40") (name "/IOB9") (class "Default")
      (node (ref "IC1") (pin "126") (pinfunction "IO_L36N_GCLK14_0_126") (pintype "passive"))
      (node (ref "P4") (pin "18") (pinfunction "18_18") (pintype "passive"))
    )
    (net (code "41") (name "/IOB10") (class "Default")
      (node (ref "IC1") (pin "124") (pinfunction "IO_L37P_GCLK13_0_124") (pintype "passive"))
      (node (ref "P4") (pin "19") (pinfunction "19_19") (pintype "passive"))
    )
    (net (code "42") (name "/IOB11") (class "Default")
      (node (ref "IC1") (pin "123") (pinfunction "IO_L37N_GCLK12_0_123") (pintype "passive"))
      (node (ref "P4") (pin "20") (pinfunction "20_20") (pintype "passive"))
    )
    (net (code "43") (name "/IOB12") (class "Default")
      (node (ref "IC1") (pin "95") (pinfunction "IO_L40P_GCLK11_1_95") (pintype "passive"))
      (node (ref "P5") (pin "1") (pinfunction "1_1") (pintype "passive"))
    )
    (net (code "44") (name "/IOB13") (class "Default")
      (node (ref "IC1") (pin "94") (pinfunction "IO_L40N_GCLK10_1_94") (pintype "passive"))
      (node (ref "P5") (pin "2") (pinfunction "2_2") (pintype "passive"))
    )
    (net (code "45") (name "/IOB14") (class "Default")
      (node (ref "IC1") (pin "119") (pinfunction "IO_L63P_SCP7_0_119") (pintype "passive"))
      (node (ref "P5") (pin "3") (pinfunction "3_3") (pintype "passive"))
    )
    (net (code "46") (name "/IOB15") (class "Default")
      (node (ref "IC1") (pin "118") (pinfunction "IO_L63N_SCP6_0_118") (pintype "passive"))
      (node (ref "P5") (pin "4") (pinfunction "4_4") (pintype "passive"))
    )
    (net (code "47") (name "/IOB16") (class "Default")
      (node (ref "IC1") (pin "117") (pinfunction "IO_L64P_SCP5_0_117") (pintype "passive"))
      (node (ref "P5") (pin "7") (pinfunction "7_7") (pintype "passive"))
    )
    (net (code "48") (name "/IOB17") (class "Default")
      (node (ref "IC1") (pin "116") (pinfunction "IO_L64N_SCP4_0_116") (pintype "passive"))
      (node (ref "P5") (pin "8") (pinfunction "8_8") (pintype "passive"))
    )
    (net (code "49") (name "/IOB18") (class "Default")
      (node (ref "IC1") (pin "115") (pinfunction "IO_L65P_SCP3_0_115") (pintype "passive"))
      (node (ref "P5") (pin "9") (pinfunction "9_9") (pintype "passive"))
    )
    (net (code "50") (name "/IOB19") (class "Default")
      (node (ref "IC1") (pin "114") (pinfunction "IO_L65N_SCP2_0_114") (pintype "passive"))
      (node (ref "P5") (pin "10") (pinfunction "10_10") (pintype "passive"))
    )
    (net (code "51") (name "/IOB20") (class "Default")
      (node (ref "IC1") (pin "112") (pinfunction "IO_L66P_SCP1_0_112") (pintype "passive"))
      (node (ref "P5") (pin "11") (pinfunction "11_11") (pintype "passive"))
    )
    (net (code "52") (name "/IOB21") (class "Default")
      (node (ref "IC1") (pin "111") (pinfunction "IO_L66N_SCP0_0_111") (pintype "passive"))
      (node (ref "P5") (pin "12") (pinfunction "12_12") (pintype "passive"))
    )
    (net (code "53") (name "/IOB22") (class "Default")
      (node (ref "IC1") (pin "102") (pinfunction "IO_L32P_1_102") (pintype "passive"))
      (node (ref "P5") (pin "13") (pinfunction "13_13") (pintype "passive"))
    )
    (net (code "54") (name "/IOB23") (class "Default")
      (node (ref "IC1") (pin "101") (pinfunction "IO_L32N_1_101") (pintype "passive"))
      (node (ref "P5") (pin "14") (pinfunction "14_14") (pintype "passive"))
    )
    (net (code "55") (name "/IOB24") (class "Default")
      (node (ref "IC1") (pin "100") (pinfunction "IO_L33P_1_100") (pintype "passive"))
      (node (ref "P5") (pin "17") (pinfunction "17_17") (pintype "passive"))
    )
    (net (code "56") (name "/IOB25") (class "Default")
      (node (ref "IC1") (pin "99") (pinfunction "IO_L33N_1_99") (pintype "passive"))
      (node (ref "P5") (pin "18") (pinfunction "18_18") (pintype "passive"))
    )
    (net (code "57") (name "/IOB26") (class "Default")
      (node (ref "IC1") (pin "98") (pinfunction "IO_L34P_1_98") (pintype "passive"))
      (node (ref "P5") (pin "19") (pinfunction "19_19") (pintype "passive"))
    )
    (net (code "58") (name "/IOB27") (class "Default")
      (node (ref "IC1") (pin "97") (pinfunction "IO_L34N_1_97") (pintype "passive"))
      (node (ref "P5") (pin "20") (pinfunction "20_20") (pintype "passive"))
    )
    (net (code "59") (name "/S CLOCK") (class "Default")
      (node (ref "IC1") (pin "70") (pinfunction "IO_L1P_CCLK_2_70") (pintype "passive"))
      (node (ref "IC2") (pin "6") (pinfunction "C_6") (pintype "passive"))
      (node (ref "R10") (pin "2") (pinfunction "2_2") (pintype "passive"))
    )
    (net (code "60") (name "/S DATA IN") (class "Default")
      (node (ref "IC1") (pin "64") (pinfunction "IO_L3N_MOSI_CSI_B_MISO0_2_64") (pintype "passive"))
      (node (ref "IC2") (pin "5") (pinfunction "DQ0_5") (pintype "passive"))
      (node (ref "R22") (pin "2") (pinfunction "2_2") (pintype "passive"))
    )
    (net (code "61") (name "/S DATA OUT") (class "Default")
      (node (ref "IC1") (pin "65") (pinfunction "IO_L3P_D0_DIN_MISO_MISO1_2_65") (pintype "passive"))
      (node (ref "IC2") (pin "2") (pinfunction "DQ1_2") (pintype "passive"))
      (node (ref "R6") (pin "2") (pinfunction "2_2") (pintype "passive"))
    )
    (net (code "62") (name "/S_SELCTn") (class "Default")
      (node (ref "IC1") (pin "38") (pinfunction "IO_L65N_CSO_B_2_38") (pintype "passive"))
      (node (ref "IC2") (pin "1") (pinfunction "S#_1") (pintype "passive"))
      (node (ref "R5") (pin "2") (pinfunction "2_2") (pintype "passive"))
    )
    (net (code "63") (name "/TDO") (class "Default")
      (node (ref "IC3") (pin "6") (pinfunction "1Y_6") (pintype "passive"))
      (node (ref "R17") (pin "1") (pinfunction "1_1") (pintype "passive"))
      (node (ref "R26") (pin "1") (pinfunction "1_1") (pintype "passive"))
    )
    (net (code "64") (name "/X DONE") (class "Default")
      (node (ref "IC1") (pin "71") (pinfunction "DONE_2_71") (pintype "passive"))
      (node (ref "R4") (pin "1") (pinfunction "1_1") (pintype "passive"))
    )
    (net (code "65") (name "/X M1") (class "Default")
      (node (ref "IC1") (pin "60") (pinfunction "IO_L13P_M1_2_60") (pintype "passive"))
      (node (ref "R25") (pin "2") (pinfunction "2_2") (pintype "passive"))
      (node (ref "S1") (pin "S0") (pinfunction "SO_S0") (pintype "output"))
    )
    (net (code "66") (name "/X PROG") (class "Default")
      (node (ref "IC1") (pin "37") (pinfunction "PROGRAM_B_2_37") (pintype "passive"))
      (node (ref "R7") (pin "1") (pinfunction "1_1") (pintype "passive"))
      (node (ref "R8") (pin "2") (pinfunction "2_2") (pintype "passive"))
      (node (ref "S2") (pin "2") (pinfunction "2_2") (pintype "passive"))
    )
    (net (code "67") (name "/X TCK") (class "Default")
      (node (ref "IC1") (pin "109") (pinfunction "TCK_109") (pintype "passive"))
      (node (ref "IC3") (pin "4") (pinfunction "2Y_4") (pintype "passive"))
      (node (ref "R18") (pin "1") (pinfunction "1_1") (pintype "passive"))
    )
    (net (code "68") (name "/X TDI") (class "Default")
      (node (ref "IC1") (pin "110") (pinfunction "TDI_110") (pintype "passive"))
      (node (ref "IC3") (pin "1") (pinfunction "1A_1") (pintype "passive"))
      (node (ref "R16") (pin "1") (pinfunction "1_1") (pintype "passive"))
    )
    (net (code "69") (name "/X TDO") (class "Default")
      (node (ref "IC1") (pin "106") (pinfunction "TDO_106") (pintype "passive"))
      (node (ref "IC4") (pin "6") (pinfunction "1Y_6") (pintype "passive"))
      (node (ref "R19") (pin "1") (pinfunction "1_1") (pintype "passive"))
    )
    (net (code "70") (name "/X TMS") (class "Default")
      (node (ref "IC1") (pin "107") (pinfunction "TMS_107") (pintype "passive"))
      (node (ref "IC4") (pin "4") (pinfunction "2Y_4") (pintype "passive"))
      (node (ref "R20") (pin "1") (pinfunction "1_1") (pintype "passive"))
    )
    (net (code "71") (name "/X_HSWAPEN") (class "Default")
      (node (ref "IC1") (pin "144") (pinfunction "IO_L1P_HSWAPEN_0_144") (pintype "passive"))
      (node (ref "R28") (pin "2") (pinfunction "2_2") (pintype "passive"))
      (node (ref "R34") (pin "2") (pinfunction "2_2") (pintype "passive"))
    )
    (net (code "72") (name "/X_INIT") (class "Default")
      (node (ref "IC1") (pin "39") (pinfunction "IO_L65P_INIT_B_2_39") (pintype "passive"))
      (node (ref "R30") (pin "2") (pinfunction "2_2") (pintype "passive"))
    )
    (net (code "73") (name "GND") (class "Default")
      (node (ref "C1") (pin "1") (pinfunction "1_1") (pintype "passive"))
      (node (ref "C10") (pin "1") (pinfunction "1_1") (pintype "passive"))
      (node (ref "C11") (pin "1") (pinfunction "1_1") (pintype "passive"))
      (node (ref "C12") (pin "1") (pinfunction "1_1") (pintype "passive"))
      (node (ref "C13") (pin "1") (pinfunction "1_1") (pintype "passive"))
      (node (ref "C14") (pin "1") (pinfunction "1_1") (pintype "passive"))
      (node (ref "C15") (pin "1") (pinfunction "1_1") (pintype "passive"))
      (node (ref "C16") (pin "1") (pinfunction "1_1") (pintype "passive"))
      (node (ref "C17") (pin "1") (pinfunction "1_1") (pintype "passive"))
      (node (ref "C18") (pin "1") (pinfunction "1_1") (pintype "passive"))
      (node (ref "C19") (pin "1") (pinfunction "1_1") (pintype "passive"))
      (node (ref "C2") (pin "1") (pinfunction "1_1") (pintype "passive"))
      (node (ref "C20") (pin "1") (pinfunction "1_1") (pintype "passive"))
      (node (ref "C21") (pin "1") (pinfunction "1_1") (pintype "passive"))
      (node (ref "C22") (pin "1") (pinfunction "1_1") (pintype "passive"))
      (node (ref "C23") (pin "1") (pinfunction "1_1") (pintype "passive"))
      (node (ref "C24") (pin "1") (pinfunction "1_1") (pintype "passive"))
      (node (ref "C25") (pin "1") (pinfunction "1_1") (pintype "passive"))
      (node (ref "C26") (pin "1") (pinfunction "1_1") (pintype "passive"))
      (node (ref "C27") (pin "1") (pinfunction "1_1") (pintype "passive"))
      (node (ref "C3") (pin "1") (pinfunction "1_1") (pintype "passive"))
      (node (ref "C4") (pin "1") (pinfunction "1_1") (pintype "passive"))
      (node (ref "C5") (pin "1") (pinfunction "1_1") (pintype "passive"))
      (node (ref "C6") (pin "1") (pinfunction "1_1") (pintype "passive"))
      (node (ref "C7") (pin "1") (pinfunction "1_1") (pintype "passive"))
      (node (ref "C8") (pin "1") (pinfunction "1_1") (pintype "passive"))
      (node (ref "C9") (pin "1") (pinfunction "1_1") (pintype "passive"))
      (node (ref "D1") (pin "3") (pinfunction "A_3") (pintype "passive"))
      (node (ref "D2") (pin "3") (pinfunction "A_3") (pintype "passive"))
      (node (ref "IC1") (pin "108") (pinfunction "GND_10_108") (pintype "passive"))
      (node (ref "IC1") (pin "113") (pinfunction "GND_11_113") (pintype "passive"))
      (node (ref "IC1") (pin "13") (pinfunction "GND_2_13") (pintype "passive"))
      (node (ref "IC1") (pin "130") (pinfunction "GND_12_130") (pintype "passive"))
      (node (ref "IC1") (pin "136") (pinfunction "GND_13_136") (pintype "passive"))
      (node (ref "IC1") (pin "25") (pinfunction "GND_3_25") (pintype "passive"))
      (node (ref "IC1") (pin "3") (pinfunction "GND_1_3") (pintype "passive"))
      (node (ref "IC1") (pin "49") (pinfunction "GND_4_49") (pintype "passive"))
      (node (ref "IC1") (pin "54") (pinfunction "GND_5_54") (pintype "passive"))
      (node (ref "IC1") (pin "68") (pinfunction "GND_6_68") (pintype "passive"))
      (node (ref "IC1") (pin "73") (pinfunction "SUSPEND_73") (pintype "passive"))
      (node (ref "IC1") (pin "77") (pinfunction "GND_7_77") (pintype "passive"))
      (node (ref "IC1") (pin "91") (pinfunction "GND_8_91") (pintype "passive"))
      (node (ref "IC1") (pin "96") (pinfunction "GND_9_96") (pintype "passive"))
      (node (ref "IC2") (pin "4") (pinfunction "VSS_4") (pintype "passive"))
      (node (ref "IC3") (pin "2") (pinfunction "GND_2") (pintype "passive"))
      (node (ref "IC4") (pin "2") (pinfunction "GND_2") (pintype "passive"))
      (node (ref "IC5") (pin "1") (pinfunction "GND_1") (pintype "passive"))
      (node (ref "L1") (pin "2") (pinfunction "K_2") (pintype "passive"))
      (node (ref "L3") (pin "2") (pinfunction "K_2") (pintype "passive"))
      (node (ref "P1") (pin "15") (pinfunction "15_15") (pintype "passive"))
      (node (ref "P1") (pin "16") (pinfunction "16_16") (pintype "passive"))
      (node (ref "P1") (pin "5") (pinfunction "5_5") (pintype "passive"))
      (node (ref "P1") (pin "6") (pinfunction "6_6") (pintype "passive"))
      (node (ref "P2") (pin "15") (pinfunction "15_15") (pintype "passive"))
      (node (ref "P2") (pin "16") (pinfunction "16_16") (pintype "passive"))
      (node (ref "P2") (pin "5") (pinfunction "5_5") (pintype "passive"))
      (node (ref "P2") (pin "6") (pinfunction "6_6") (pintype "passive"))
      (node (ref "P3") (pin "1") (pinfunction "1_1") (pintype "passive"))
      (node (ref "P3") (pin "11") (pinfunction "11_11") (pintype "passive"))
      (node (ref "P3") (pin "13") (pinfunction "13_13") (pintype "passive"))
      (node (ref "P3") (pin "3") (pinfunction "3_3") (pintype "passive"))
      (node (ref "P3") (pin "5") (pinfunction "5_5") (pintype "passive"))
      (node (ref "P3") (pin "7") (pinfunction "7_7") (pintype "passive"))
      (node (ref "P3") (pin "9") (pinfunction "9_9") (pintype "passive"))
      (node (ref "P4") (pin "15") (pinfunction "15_15") (pintype "passive"))
      (node (ref "P4") (pin "16") (pinfunction "16_16") (pintype "passive"))
      (node (ref "P4") (pin "5") (pinfunction "5_5") (pintype "passive"))
      (node (ref "P4") (pin "6") (pinfunction "6_6") (pintype "passive"))
      (node (ref "P5") (pin "15") (pinfunction "15_15") (pintype "passive"))
      (node (ref "P5") (pin "16") (pinfunction "16_16") (pintype "passive"))
      (node (ref "P5") (pin "5") (pinfunction "5_5") (pintype "passive"))
      (node (ref "P5") (pin "6") (pinfunction "6_6") (pintype "passive"))
      (node (ref "R29") (pin "1") (pinfunction "1_1") (pintype "passive"))
      (node (ref "R3") (pin "2") (pinfunction "2_2") (pintype "passive"))
      (node (ref "R34") (pin "1") (pinfunction "1_1") (pintype "passive"))
      (node (ref "S1") (pin "SI") (pinfunction "S!_SI") (pintype "input"))
      (node (ref "S2") (pin "1") (pinfunction "1_1") (pintype "passive"))
      (node (ref "Y1") (pin "2") (pinfunction "GROUND_2") (pintype "passive"))
    )
    (net (code "74") (name "Net-(C27-Pad2)") (class "Default")
      (node (ref "C27") (pin "2") (pinfunction "2_2") (pintype "passive"))
      (node (ref "R8") (pin "1") (pinfunction "1_1") (pintype "passive"))
    )
    (net (code "75") (name "Net-(IC3-2A)") (class "Default")
      (node (ref "IC3") (pin "3") (pinfunction "2A_3") (pintype "passive"))
      (node (ref "P3") (pin "6") (pinfunction "6_6") (pintype "passive"))
      (node (ref "R15") (pin "1") (pinfunction "1_1") (pintype "passive"))
    )
    (net (code "76") (name "Net-(IC4-1A)") (class "Default")
      (node (ref "IC4") (pin "1") (pinfunction "1A_1") (pintype "passive"))
      (node (ref "R14") (pin "1") (pinfunction "1_1") (pintype "passive"))
      (node (ref "R27") (pin "1") (pinfunction "1_1") (pintype "passive"))
    )
    (net (code "77") (name "Net-(IC4-2A)") (class "Default")
      (node (ref "IC4") (pin "3") (pinfunction "2A_3") (pintype "passive"))
      (node (ref "R13") (pin "1") (pinfunction "1_1") (pintype "passive"))
      (node (ref "R21") (pin "1") (pinfunction "1_1") (pintype "passive"))
    )
    (net (code "78") (name "Net-(L1-A)") (class "Default")
      (node (ref "L1") (pin "1") (pinfunction "A_1") (pintype "passive"))
      (node (ref "R4") (pin "2") (pinfunction "2_2") (pintype "passive"))
    )
    (net (code "79") (name "Net-(L3-A)") (class "Default")
      (node (ref "L3") (pin "1") (pinfunction "A_1") (pintype "passive"))
      (node (ref "R33") (pin "1") (pinfunction "1_1") (pintype "passive"))
    )
    (net (code "80") (name "Net-(P1-Pad3)") (class "Default")
      (node (ref "P1") (pin "3") (pinfunction "3_3") (pintype "passive"))
      (node (ref "P1") (pin "4") (pinfunction "4_4") (pintype "passive"))
    )
    (net (code "81") (name "Net-(P3-Pad4)") (class "Default")
      (node (ref "P3") (pin "4") (pinfunction "4_4") (pintype "passive"))
      (node (ref "R21") (pin "2") (pinfunction "2_2") (pintype "passive"))
    )
    (net (code "82") (name "Net-(P3-Pad8)") (class "Default")
      (node (ref "P3") (pin "8") (pinfunction "8_8") (pintype "passive"))
      (node (ref "R26") (pin "2") (pinfunction "2_2") (pintype "passive"))
    )
    (net (code "83") (name "Net-(P3-Pad10)") (class "Default")
      (node (ref "P3") (pin "10") (pinfunction "10_10") (pintype "passive"))
      (node (ref "R27") (pin "2") (pinfunction "2_2") (pintype "passive"))
    )
    (net (code "84") (name "Net-(P4-Pad3)") (class "Default")
      (node (ref "P4") (pin "3") (pinfunction "3_3") (pintype "passive"))
      (node (ref "P4") (pin "4") (pinfunction "4_4") (pintype "passive"))
    )
    (net (code "85") (name "Net-(Y1-CONTROL)") (class "Default")
      (node (ref "R3") (pin "1") (pinfunction "1_1") (pintype "passive"))
      (node (ref "Y1") (pin "1") (pinfunction "CONTROL_1") (pintype "passive"))
    )
    (net (code "86") (name "Net-(Y1-OUTPUT)") (class "Default")
      (node (ref "R1") (pin "2") (pinfunction "2_2") (pintype "passive"))
      (node (ref "R2") (pin "2") (pinfunction "2_2") (pintype "passive"))
      (node (ref "Y1") (pin "3") (pinfunction "OUTPUT_3") (pintype "passive"))
    )
    (net (code "88") (name "V12") (class "Default")
      (node (ref "C17") (pin "2") (pinfunction "2_2") (pintype "passive"))
      (node (ref "C23") (pin "2") (pinfunction "2_2") (pintype "passive"))
      (node (ref "C24") (pin "2") (pinfunction "2_2") (pintype "passive"))
      (node (ref "C25") (pin "2") (pinfunction "2_2") (pintype "passive"))
      (node (ref "C26") (pin "2") (pinfunction "2_2") (pintype "passive"))
      (node (ref "IC1") (pin "128") (pinfunction "VCCINT_5_128") (pintype "passive"))
      (node (ref "IC1") (pin "19") (pinfunction "VCCINT_1_19") (pintype "passive"))
      (node (ref "IC1") (pin "28") (pinfunction "VCCINT_2_28") (pintype "passive"))
      (node (ref "IC1") (pin "52") (pinfunction "VCCINT_3_52") (pintype "passive"))
      (node (ref "IC1") (pin "89") (pinfunction "VCCINT_4_89") (pintype "passive"))
      (node (ref "IC5") (pin "2") (pinfunction "OUTPUT_1_2") (pintype "passive"))
      (node (ref "IC5") (pin "4") (pinfunction "OUTPUT_2_4") (pintype "passive"))
      (node (ref "R29") (pin "2") (pinfunction "2_2") (pintype "passive"))
    )
    (net (code "89") (name "V33A") (class "Default")
      (node (ref "C1") (pin "2") (pinfunction "2_2") (pintype "passive"))
      (node (ref "C10") (pin "2") (pinfunction "2_2") (pintype "passive"))
      (node (ref "C11") (pin "2") (pinfunction "2_2") (pintype "passive"))
      (node (ref "C12") (pin "2") (pinfunction "2_2") (pintype "passive"))
      (node (ref "C13") (pin "2") (pinfunction "2_2") (pintype "passive"))
      (node (ref "C14") (pin "2") (pinfunction "2_2") (pintype "passive"))
      (node (ref "C15") (pin "2") (pinfunction "2_2") (pintype "passive"))
      (node (ref "C16") (pin "2") (pinfunction "2_2") (pintype "passive"))
      (node (ref "C18") (pin "2") (pinfunction "2_2") (pintype "passive"))
      (node (ref "C19") (pin "2") (pinfunction "2_2") (pintype "passive"))
      (node (ref "C2") (pin "2") (pinfunction "2_2") (pintype "passive"))
      (node (ref "C20") (pin "2") (pinfunction "2_2") (pintype "passive"))
      (node (ref "C21") (pin "2") (pinfunction "2_2") (pintype "passive"))
      (node (ref "C22") (pin "2") (pinfunction "2_2") (pintype "passive"))
      (node (ref "C3") (pin "2") (pinfunction "2_2") (pintype "passive"))
      (node (ref "C4") (pin "2") (pinfunction "2_2") (pintype "passive"))
      (node (ref "C5") (pin "2") (pinfunction "2_2") (pintype "passive"))
      (node (ref "C6") (pin "2") (pinfunction "2_2") (pintype "passive"))
      (node (ref "C7") (pin "2") (pinfunction "2_2") (pintype "passive"))
      (node (ref "C8") (pin "2") (pinfunction "2_2") (pintype "passive"))
      (node (ref "C9") (pin "2") (pinfunction "2_2") (pintype "passive"))
      (node (ref "D1") (pin "1") (pinfunction "K_1") (pintype "passive"))
      (node (ref "D2") (pin "1") (pinfunction "K_1") (pintype "passive"))
      (node (ref "IC1") (pin "103") (pinfunction "VCCO_1_3_103") (pintype "passive"))
      (node (ref "IC1") (pin "122") (pinfunction "VCCO_0_1_122") (pintype "passive"))
      (node (ref "IC1") (pin "125") (pinfunction "VCCO_0_2_125") (pintype "passive"))
      (node (ref "IC1") (pin "129") (pinfunction "VCCAUX_5_129") (pintype "passive"))
      (node (ref "IC1") (pin "135") (pinfunction "VCCO_0_3_135") (pintype "passive"))
      (node (ref "IC1") (pin "18") (pinfunction "VCCO_3_2_18") (pintype "passive"))
      (node (ref "IC1") (pin "20") (pinfunction "VCCAUX_1_20") (pintype "passive"))
      (node (ref "IC1") (pin "31") (pinfunction "VCCO_3_3_31") (pintype "passive"))
      (node (ref "IC1") (pin "36") (pinfunction "VCCAUX_2_36") (pintype "passive"))
      (node (ref "IC1") (pin "4") (pinfunction "VCCO_3_1_4") (pintype "passive"))
      (node (ref "IC1") (pin "42") (pinfunction "VCCO_2_1_42") (pintype "passive"))
      (node (ref "IC1") (pin "53") (pinfunction "VCCAUX_3_53") (pintype "passive"))
      (node (ref "IC1") (pin "63") (pinfunction "VCCO_2_2_63") (pintype "passive"))
      (node (ref "IC1") (pin "69") (pinfunction "IO_L1N_M0_CMPMISO_2_69") (pintype "passive"))
      (node (ref "IC1") (pin "76") (pinfunction "VCCO_1_1_76") (pintype "passive"))
      (node (ref "IC1") (pin "86") (pinfunction "VCCO_1_2_86") (pintype "passive"))
      (node (ref "IC1") (pin "90") (pinfunction "VCCAUX_4_90") (pintype "passive"))
      (node (ref "IC2") (pin "3") (pinfunction "W#_3") (pintype "passive"))
      (node (ref "IC2") (pin "7") (pinfunction "HOLD#_7") (pintype "passive"))
      (node (ref "IC2") (pin "8") (pinfunction "VCC_8") (pintype "passive"))
      (node (ref "IC3") (pin "5") (pinfunction "VCC_5") (pintype "passive"))
      (node (ref "IC4") (pin "5") (pinfunction "VCC_5") (pintype "passive"))
      (node (ref "IC5") (pin "3") (pinfunction "INPUT_3") (pintype "passive"))
      (node (ref "P1") (pin "1") (pinfunction "1_1") (pintype "passive"))
      (node (ref "P1") (pin "2") (pinfunction "2_2") (pintype "passive"))
      (node (ref "P3") (pin "2") (pinfunction "2_2") (pintype "passive"))
      (node (ref "P4") (pin "1") (pinfunction "1_1") (pintype "passive"))
      (node (ref "P4") (pin "2") (pinfunction "2_2") (pintype "passive"))
      (node (ref "R10") (pin "1") (pinfunction "1_1") (pintype "passive"))
      (node (ref "R13") (pin "2") (pinfunction "2_2") (pintype "passive"))
      (node (ref "R14") (pin "2") (pinfunction "2_2") (pintype "passive"))
      (node (ref "R15") (pin "2") (pinfunction "2_2") (pintype "passive"))
      (node (ref "R16") (pin "2") (pinfunction "2_2") (pintype "passive"))
      (node (ref "R17") (pin "2") (pinfunction "2_2") (pintype "passive"))
      (node (ref "R18") (pin "2") (pinfunction "2_2") (pintype "passive"))
      (node (ref "R19") (pin "2") (pinfunction "2_2") (pintype "passive"))
      (node (ref "R20") (pin "2") (pinfunction "2_2") (pintype "passive"))
      (node (ref "R22") (pin "1") (pinfunction "1_1") (pintype "passive"))
      (node (ref "R25") (pin "1") (pinfunction "1_1") (pintype "passive"))
      (node (ref "R28") (pin "1") (pinfunction "1_1") (pintype "passive"))
      (node (ref "R30") (pin "1") (pinfunction "1_1") (pintype "passive"))
      (node (ref "R33") (pin "2") (pinfunction "2_2") (pintype "passive"))
      (node (ref "R5") (pin "1") (pinfunction "1_1") (pintype "passive"))
      (node (ref "R6") (pin "1") (pinfunction "1_1") (pintype "passive"))
      (node (ref "R7") (pin "2") (pinfunction "2_2") (pintype "passive"))
      (node (ref "Y1") (pin "4") (pinfunction "VCC_4") (pintype "passive"))
    )
    (net (code "90") (name "unconnected-(IC1-CMPCS_B_2-Pad72)") (class "Default")
      (node (ref "IC1") (pin "72") (pinfunction "CMPCS_B_2_72") (pintype "passive+no_connect"))
    )
    (net (code "91") (name "unconnected-(IC1-IO_L1N_VREF_0-Pad143)") (class "Default")
      (node (ref "IC1") (pin "143") (pinfunction "IO_L1N_VREF_0_143") (pintype "passive+no_connect"))
    )
    (net (code "92") (name "unconnected-(IC1-IO_L1N_VREF_1-Pad104)") (class "Default")
      (node (ref "IC1") (pin "104") (pinfunction "IO_L1N_VREF_1_104") (pintype "passive+no_connect"))
    )
    (net (code "93") (name "unconnected-(IC1-IO_L1N_VREF_3-Pad34)") (class "Default")
      (node (ref "IC1") (pin "34") (pinfunction "IO_L1N_VREF_3_34") (pintype "passive+no_connect"))
    )
    (net (code "94") (name "unconnected-(IC1-IO_L1P_1-Pad105)") (class "Default")
      (node (ref "IC1") (pin "105") (pinfunction "IO_L1P_1_105") (pintype "passive+no_connect"))
    )
    (net (code "95") (name "unconnected-(IC1-IO_L1P_3-Pad35)") (class "Default")
      (node (ref "IC1") (pin "35") (pinfunction "IO_L1P_3_35") (pintype "passive+no_connect"))
    )
    (net (code "96") (name "unconnected-(IC1-IO_L2N_0-Pad141)") (class "Default")
      (node (ref "IC1") (pin "141") (pinfunction "IO_L2N_0_141") (pintype "passive+no_connect"))
    )
    (net (code "97") (name "unconnected-(IC1-IO_L2N_3-Pad32)") (class "Default")
      (node (ref "IC1") (pin "32") (pinfunction "IO_L2N_3_32") (pintype "passive+no_connect"))
    )
    (net (code "98") (name "unconnected-(IC1-IO_L2P_0-Pad142)") (class "Default")
      (node (ref "IC1") (pin "142") (pinfunction "IO_L2P_0_142") (pintype "passive+no_connect"))
    )
    (net (code "99") (name "unconnected-(IC1-IO_L2P_3-Pad33)") (class "Default")
      (node (ref "IC1") (pin "33") (pinfunction "IO_L2P_3_33") (pintype "passive+no_connect"))
    )
    (net (code "100") (name "unconnected-(IC1-IO_L13N_D10_2-Pad59)") (class "Default")
      (node (ref "IC1") (pin "59") (pinfunction "IO_L13N_D10_2_59") (pintype "passive+no_connect"))
    )
    (net (code "101") (name "unconnected-(IC1-IO_L36N_3-Pad29)") (class "Default")
      (node (ref "IC1") (pin "29") (pinfunction "IO_L36N_3_29") (pintype "passive+no_connect"))
    )
    (net (code "102") (name "unconnected-(IC1-IO_L36P_3-Pad30)") (class "Default")
      (node (ref "IC1") (pin "30") (pinfunction "IO_L36P_3_30") (pintype "passive+no_connect"))
    )
    (net (code "103") (name "unconnected-(IC1-IO_L37N_3-Pad26)") (class "Default")
      (node (ref "IC1") (pin "26") (pinfunction "IO_L37N_3_26") (pintype "passive+no_connect"))
    )
    (net (code "104") (name "unconnected-(IC1-IO_L37P_3-Pad27)") (class "Default")
      (node (ref "IC1") (pin "27") (pinfunction "IO_L37P_3_27") (pintype "passive+no_connect"))
    )
    (net (code "105") (name "unconnected-(IC1-IO_L41N_GCLK8_1-Pad92)") (class "Default")
      (node (ref "IC1") (pin "92") (pinfunction "IO_L41N_GCLK8_1_92") (pintype "passive+no_connect"))
    )
    (net (code "106") (name "unconnected-(IC1-IO_L41P_GCLK9_IRDY1_1-Pad93)") (class "Default")
      (node (ref "IC1") (pin "93") (pinfunction "IO_L41P_GCLK9_IRDY1_1_93") (pintype "passive+no_connect"))
    )
    (net (code "107") (name "unconnected-(IC1-IO_L41P_GCLK27_3-Pad24)") (class "Default")
      (node (ref "IC1") (pin "24") (pinfunction "IO_L41P_GCLK27_3_24") (pintype "passive+no_connect"))
    )
    (net (code "108") (name "unconnected-(IC1-IO_L42N_GCLK6_TRDY1_1-Pad87)") (class "Default")
      (node (ref "IC1") (pin "87") (pinfunction "IO_L42N_GCLK6_TRDY1_1_87") (pintype "passive+no_connect"))
    )
    (net (code "109") (name "unconnected-(IC1-IO_L42N_GCLK24_3-Pad21)") (class "Default")
      (node (ref "IC1") (pin "21") (pinfunction "IO_L42N_GCLK24_3_21") (pintype "passive+no_connect"))
    )
    (net (code "110") (name "unconnected-(IC1-IO_L42P_GCLK7_1-Pad88)") (class "Default")
      (node (ref "IC1") (pin "88") (pinfunction "IO_L42P_GCLK7_1_88") (pintype "passive+no_connect"))
    )
    (net (code "111") (name "unconnected-(IC1-IO_L42P_GCLK25_TRDY2_3-Pad22)") (class "Default")
      (node (ref "IC1") (pin "22") (pinfunction "IO_L42P_GCLK25_TRDY2_3_22") (pintype "passive+no_connect"))
    )
    (net (code "112") (name "unconnected-(IC1-IO_L43N_GCLK4_1-Pad84)") (class "Default")
      (node (ref "IC1") (pin "84") (pinfunction "IO_L43N_GCLK4_1_84") (pintype "passive+no_connect"))
    )
    (net (code "113") (name "unconnected-(IC1-IO_L43N_GCLK22_IRDY2_3-Pad16)") (class "Default")
      (node (ref "IC1") (pin "16") (pinfunction "IO_L43N_GCLK22_IRDY2_3_16") (pintype "passive+no_connect"))
    )
    (net (code "114") (name "unconnected-(IC1-IO_L43P_GCLK5_1-Pad85)") (class "Default")
      (node (ref "IC1") (pin "85") (pinfunction "IO_L43P_GCLK5_1_85") (pintype "passive+no_connect"))
    )
    (net (code "115") (name "unconnected-(IC1-IO_L43P_GCLK23_3-Pad17)") (class "Default")
      (node (ref "IC1") (pin "17") (pinfunction "IO_L43P_GCLK23_3_17") (pintype "passive+no_connect"))
    )
    (net (code "116") (name "unconnected-(IC1-IO_L44P_GCLK21_3-Pad15)") (class "Default")
      (node (ref "IC1") (pin "15") (pinfunction "IO_L44P_GCLK21_3_15") (pintype "passive+no_connect"))
    )
    (net (code "117") (name "unconnected-(IC1-IO_L45N_1-Pad82)") (class "Default")
      (node (ref "IC1") (pin "82") (pinfunction "IO_L45N_1_82") (pintype "passive+no_connect"))
    )
    (net (code "118") (name "unconnected-(IC1-IO_L45P_1-Pad83)") (class "Default")
      (node (ref "IC1") (pin "83") (pinfunction "IO_L45P_1_83") (pintype "passive+no_connect"))
    )
    (net (code "119") (name "unconnected-(IC1-IO_L46N_1-Pad80)") (class "Default")
      (node (ref "IC1") (pin "80") (pinfunction "IO_L46N_1_80") (pintype "passive+no_connect"))
    )
    (net (code "120") (name "unconnected-(IC1-IO_L46P_1-Pad81)") (class "Default")
      (node (ref "IC1") (pin "81") (pinfunction "IO_L46P_1_81") (pintype "passive+no_connect"))
    )
    (net (code "121") (name "unconnected-(IC1-IO_L47N_1-Pad78)") (class "Default")
      (node (ref "IC1") (pin "78") (pinfunction "IO_L47N_1_78") (pintype "passive+no_connect"))
    )
    (net (code "122") (name "unconnected-(IC1-IO_L47P_1-Pad79)") (class "Default")
      (node (ref "IC1") (pin "79") (pinfunction "IO_L47P_1_79") (pintype "passive+no_connect"))
    )
    (net (code "123") (name "unconnected-(IC1-IO_L62N_VREF_0-Pad120)") (class "Default")
      (node (ref "IC1") (pin "120") (pinfunction "IO_L62N_VREF_0_120") (pintype "passive+no_connect"))
    )
    (net (code "124") (name "unconnected-(IC1-IO_L62P_0-Pad121)") (class "Default")
      (node (ref "IC1") (pin "121") (pinfunction "IO_L62P_0_121") (pintype "passive+no_connect"))
    )
    (net (code "125") (name "unconnected-(IC1-IO_L74N_DOUT_BUSY_1-Pad74)") (class "Default")
      (node (ref "IC1") (pin "74") (pinfunction "IO_L74N_DOUT_BUSY_1_74") (pintype "passive+no_connect"))
    )
    (net (code "126") (name "unconnected-(IC1-IO_L74P_AWAKE_1-Pad75)") (class "Default")
      (node (ref "IC1") (pin "75") (pinfunction "IO_L74P_AWAKE_1_75") (pintype "passive+no_connect"))
    )
    (net (code "127") (name "unconnected-(P3-Pad12)") (class "Default")
      (node (ref "P3") (pin "12") (pinfunction "12_12") (pintype "passive+no_connect"))
    )
    (net (code "128") (name "unconnected-(P3-Pad14)") (class "Default")
      (node (ref "P3") (pin "14") (pinfunction "14_14") (pintype "passive+no_connect"))
    )
  )
)
